# FL-Ver0_6.net
KiCad netlist of a schematic drawn in EAGLE
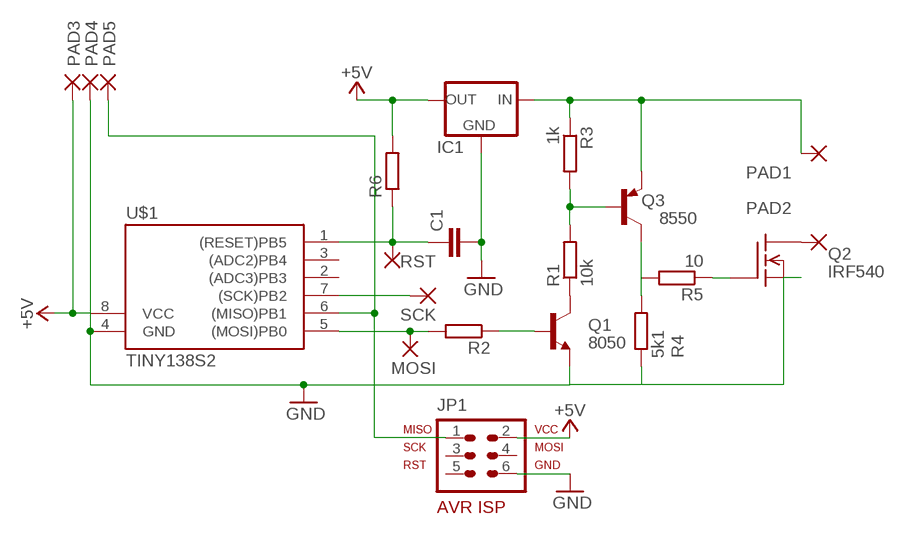
[diagram p0: schematic, sheet 1]

(export (version "E")
  (design (tool "Eeschema 10.0.6"))
  (components
    (comp (ref "C1")
      (value "C-EUC0805")
      (footprint "eagle-import:C0805")
      (libsource (lib "eagle-import") (part "C-EUC0805"))
    )
    (comp (ref "IC1")
      (value "78MXXSDPACK")
      (footprint "eagle-import:DPACK")
      (libsource (lib "eagle-import") (part "78MXXSDPACK"))
    )
    (comp (ref "JP1")
      (value "AVR-ISP-6VERT")
      (footprint "eagle-import:AVR-ISP-6")
      (libsource (lib "eagle-import") (part "AVR-ISP-6VERT"))
    )
    (comp (ref "MOSI")
      (value "1,6/0,8")
      (footprint "eagle-import:1,6_0,8")
      (libsource (lib "eagle-import") (part "1,6/0,8"))
    )
    (comp (ref "PAD1")
      (value "SMD5")
      (footprint "eagle-import:SMD2,54-5,08")
      (libsource (lib "eagle-import") (part "SMD5"))
    )
    (comp (ref "PAD2")
      (value "SMD5")
      (footprint "eagle-import:SMD2,54-5,08")
      (libsource (lib "eagle-import") (part "SMD5"))
    )
    (comp (ref "PAD3")
      (value "SMD5")
      (footprint "eagle-import:SMD2,54-5,08")
      (libsource (lib "eagle-import") (part "SMD5"))
    )
    (comp (ref "PAD4")
      (value "SMD5")
      (footprint "eagle-import:SMD2,54-5,08")
      (libsource (lib "eagle-import") (part "SMD5"))
    )
    (comp (ref "PAD5")
      (value "SMD5")
      (footprint "eagle-import:SMD2,54-5,08")
      (libsource (lib "eagle-import") (part "SMD5"))
    )
    (comp (ref "Q1")
      (value "8050")
      (footprint "eagle-import:TO92-EBC")
      (libsource (lib "eagle-import") (part "-NPN-TO92-EBC"))
    )
    (comp (ref "Q2")
      (value "IRF540")
      (footprint "eagle-import:TO220")
      (libsource (lib "eagle-import") (part "IRF540"))
    )
    (comp (ref "Q3")
      (value "8550")
      (footprint "eagle-import:TO92-EBC")
      (libsource (lib "eagle-import") (part "-PNP-TO92-EBCBC327-16"))
    )
    (comp (ref "R1")
      (value "10k")
      (footprint "eagle-import:0309_12")
      (libsource (lib "eagle-import") (part "R-EU_0309/12"))
    )
    (comp (ref "R2")
      (value "R-EU_0309/12")
      (footprint "eagle-import:0309_12")
      (libsource (lib "eagle-import") (part "R-EU_0309/12"))
    )
    (comp (ref "R3")
      (value "1k")
      (footprint "eagle-import:0309_12")
      (libsource (lib "eagle-import") (part "R-EU_0309/12"))
    )
    (comp (ref "R4")
      (value "5k1")
      (footprint "eagle-import:0309_12")
      (libsource (lib "eagle-import") (part "R-EU_0309/12"))
    )
    (comp (ref "R5")
      (value "10")
      (footprint "eagle-import:0309_12")
      (libsource (lib "eagle-import") (part "R-EU_0309/12"))
    )
    (comp (ref "R6")
      (value "R-EU_M0805")
      (footprint "eagle-import:M0805")
      (libsource (lib "eagle-import") (part "R-EU_M0805"))
    )
    (comp (ref "RST")
      (value "1,6/0,8")
      (footprint "eagle-import:1,6_0,8")
      (libsource (lib "eagle-import") (part "1,6/0,8"))
    )
    (comp (ref "SCK")
      (value "1,6/0,8")
      (footprint "eagle-import:1,6_0,8")
      (libsource (lib "eagle-import") (part "1,6/0,8"))
    )
    (comp (ref "U$1")
      (value "TINY138S2")
      (footprint "eagle-import:SO08")
      (libsource (lib "eagle-import") (part "TINY138S2"))
    )
  )
  (nets
    (net (code "1") (name "+5V") (class "Default")
      (node (ref "IC1") (pin "3") (pinfunction "OUT_3") (pintype "passive"))
      (node (ref "JP1") (pin "2") (pinfunction "2_2") (pintype "passive"))
      (node (ref "PAD3") (pin "1") (pinfunction "P_1") (pintype "passive"))
      (node (ref "R6") (pin "2") (pinfunction "2_2") (pintype "passive"))
      (node (ref "U$1") (pin "8") (pinfunction "VCC_8") (pintype "power_in"))
    )
    (net (code "2") (name "GND") (class "Default")
      (node (ref "C1") (pin "2") (pinfunction "2_2") (pintype "passive"))
      (node (ref "IC1") (pin "2") (pinfunction "GND_2") (pintype "input"))
      (node (ref "JP1") (pin "6") (pinfunction "6_6") (pintype "passive"))
      (node (ref "PAD4") (pin "1") (pinfunction "P_1") (pintype "passive"))
      (node (ref "Q1") (pin "E") (pinfunction "E_E") (pintype "passive"))
      (node (ref "Q2") (pin "3") (pinfunction "S_3") (pintype "passive"))
      (node (ref "R4") (pin "1") (pinfunction "1_1") (pintype "passive"))
      (node (ref "U$1") (pin "4") (pinfunction "GND_4") (pintype "power_in"))
    )
    (net (code "3") (name "Net-(IC1-IN)") (class "Default")
      (node (ref "IC1") (pin "1") (pinfunction "IN_1") (pintype "input"))
      (node (ref "PAD1") (pin "1") (pinfunction "P_1") (pintype "passive"))
      (node (ref "Q3") (pin "E") (pinfunction "E_E") (pintype "passive"))
      (node (ref "R3") (pin "1") (pinfunction "1_1") (pintype "passive"))
    )
    (net (code "4") (name "Net-(MOSI-P)") (class "Default")
      (node (ref "MOSI") (pin "1") (pinfunction "P_1") (pintype "passive"))
      (node (ref "R2") (pin "2") (pinfunction "2_2") (pintype "passive"))
      (node (ref "U$1") (pin "5") (pinfunction "(MOSI)PB0_5") (pintype "bidirectional"))
    )
    (net (code "5") (name "Net-(PAD2-P)") (class "Default")
      (node (ref "PAD2") (pin "1") (pinfunction "P_1") (pintype "passive"))
      (node (ref "Q2") (pin "2") (pinfunction "D_2") (pintype "passive"))
    )
    (net (code "6") (name "Net-(PAD5-P)") (class "Default")
      (node (ref "JP1") (pin "1") (pinfunction "1_1") (pintype "passive"))
      (node (ref "PAD5") (pin "1") (pinfunction "P_1") (pintype "passive"))
      (node (ref "U$1") (pin "6") (pinfunction "(MISO)PB1_6") (pintype "bidirectional"))
    )
    (net (code "7") (name "Net-(Q1-PadB)") (class "Default")
      (node (ref "Q1") (pin "B") (pinfunction "B_B") (pintype "passive"))
      (node (ref "R2") (pin "1") (pinfunction "1_1") (pintype "passive"))
    )
    (net (code "8") (name "Net-(Q1-PadC)") (class "Default")
      (node (ref "Q1") (pin "C") (pinfunction "C_C") (pintype "passive"))
      (node (ref "R1") (pin "1") (pinfunction "1_1") (pintype "passive"))
    )
    (net (code "9") (name "Net-(Q2-G)") (class "Default")
      (node (ref "Q2") (pin "1") (pinfunction "G_1") (pintype "passive"))
      (node (ref "R5") (pin "1") (pinfunction "1_1") (pintype "passive"))
    )
    (net (code "10") (name "Net-(Q3-PadB)") (class "Default")
      (node (ref "Q3") (pin "B") (pinfunction "B_B") (pintype "passive"))
      (node (ref "R1") (pin "2") (pinfunction "2_2") (pintype "passive"))
      (node (ref "R3") (pin "2") (pinfunction "2_2") (pintype "passive"))
    )
    (net (code "11") (name "Net-(Q3-PadC)") (class "Default")
      (node (ref "Q3") (pin "C") (pinfunction "C_C") (pintype "passive"))
      (node (ref "R4") (pin "2") (pinfunction "2_2") (pintype "passive"))
      (node (ref "R5") (pin "2") (pinfunction "2_2") (pintype "passive"))
    )
    (net (code "12") (name "Net-(RST-P)") (class "Default")
      (node (ref "C1") (pin "1") (pinfunction "1_1") (pintype "passive"))
      (node (ref "R6") (pin "1") (pinfunction "1_1") (pintype "passive"))
      (node (ref "RST") (pin "1") (pinfunction "P_1") (pintype "passive"))
      (node (ref "U$1") (pin "1") (pinfunction "(RESET)PB5_1") (pintype "bidirectional"))
    )
    (net (code "13") (name "Net-(SCK-P)") (class "Default")
      (node (ref "SCK") (pin "1") (pinfunction "P_1") (pintype "passive"))
      (node (ref "U$1") (pin "7") (pinfunction "(SCK)PB2_7") (pintype "bidirectional"))
    )
    (net (code "14") (name "unconnected-(JP1-Pad3)") (class "Default")
      (node (ref "JP1") (pin "3") (pinfunction "3_3") (pintype "passive"))
    )
    (net (code "15") (name "unconnected-(JP1-Pad4)") (class "Default")
      (node (ref "JP1") (pin "4") (pinfunction "4_4") (pintype "passive"))
    )
    (net (code "16") (name "unconnected-(JP1-Pad5)") (class "Default")
      (node (ref "JP1") (pin "5") (pinfunction "5_5") (pintype "passive"))
    )
    (net (code "17") (name "unconnected-(U$1-(ADC2)PB4-Pad3)") (class "Default")
      (node (ref "U$1") (pin "3") (pinfunction "(ADC2)PB4_3") (pintype "bidirectional"))
    )
    (net (code "18") (name "unconnected-(U$1-(ADC3)PB3-Pad2)") (class "Default")
      (node (ref "U$1") (pin "2") (pinfunction "(ADC3)PB3_2") (pintype "bidirectional"))
    )
  )
)
